# Temp_V_DC_Measurement.net
KiCad netlist of a schematic drawn in Altium Designer
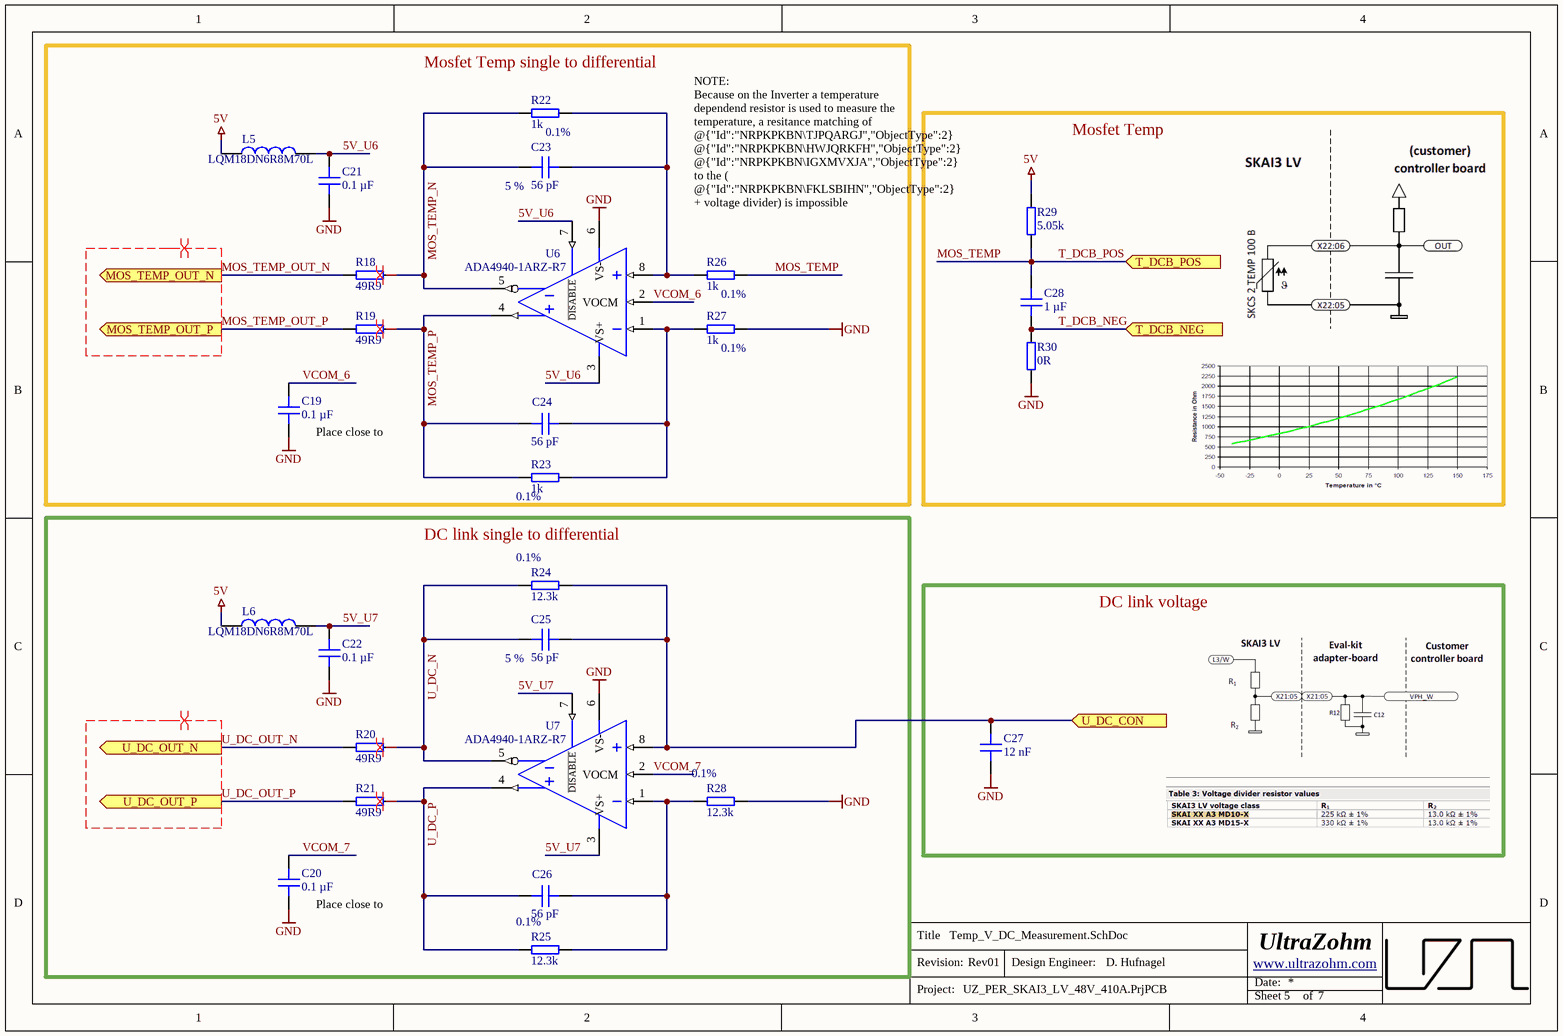
[diagram p0: Temp_V_DC_Measurement.SchDoc]

(export (version "E")
  (design (tool "Eeschema 10.0.6"))
  (components
    (comp (ref "C19")
      (value "0.1 µF")
      (footprint "C_0603")
      (description "Capacitor 0603, 50 VDC, 0.1 µF, X7R")
      (fields
        (field (name "MANUFACTURER PART NUMBER") "C0603X104K5RAC7411")
        (field (name "MANUFACTURER") "KEMET")
        (field (name "CREATED FROM") "MGremer")
      )
      (libsource (lib "user") (part "Capacitor"))
    )
    (comp (ref "C20")
      (value "0.1 µF")
      (footprint "C_0603")
      (description "Capacitor 0603, 50 VDC, 0.1 µF, X7R")
      (fields
        (field (name "MANUFACTURER PART NUMBER") "C0603X104K5RAC7411")
        (field (name "MANUFACTURER") "KEMET")
        (field (name "CREATED FROM") "MGremer")
      )
      (libsource (lib "user") (part "Capacitor"))
    )
    (comp (ref "C21")
      (value "0.1 µF")
      (footprint "C_0603")
      (description "Capacitor 0603, 50 VDC, 0.1 µF, X7R")
      (fields
        (field (name "MANUFACTURER PART NUMBER") "C0603X104K5RAC7411")
        (field (name "MANUFACTURER") "KEMET")
        (field (name "CREATED FROM") "MGremer")
      )
      (libsource (lib "user") (part "Capacitor"))
    )
    (comp (ref "C22")
      (value "0.1 µF")
      (footprint "C_0603")
      (description "Capacitor 0603, 50 VDC, 0.1 µF, X7R")
      (fields
        (field (name "MANUFACTURER PART NUMBER") "C0603X104K5RAC7411")
        (field (name "MANUFACTURER") "KEMET")
        (field (name "CREATED FROM") "MGremer")
      )
      (libsource (lib "user") (part "Capacitor"))
    )
    (comp (ref "C23")
      (value "56 pF")
      (footprint "C_0603")
      (description "Capacitor 0603, 50 VDC, 56 pF, C0G")
      (fields
        (field (name "MANUFACTURER PART NUMBER") "CL10C560JB8NNNC")
        (field (name "MANUFACTURER") "Samsung Electro-Mechanics")
        (field (name "TOLERANCE") "5 %")
        (field (name "CREATED FROM") "DHufnagel")
      )
      (libsource (lib "user") (part "Capacitor"))
    )
    (comp (ref "C24")
      (value "56 pF")
      (footprint "C_0603")
      (description "Capacitor 0603, 50 VDC, 56 pF, C0G")
      (fields
        (field (name "MANUFACTURER PART NUMBER") "CL10C560JB8NNNC")
        (field (name "MANUFACTURER") "Samsung Electro-Mechanics")
        (field (name "CREATED FROM") "DHufnagel")
      )
      (libsource (lib "user") (part "Capacitor"))
    )
    (comp (ref "C25")
      (value "56 pF")
      (footprint "C_0603")
      (description "Capacitor 0603, 50 VDC, 56 pF, C0G")
      (fields
        (field (name "MANUFACTURER PART NUMBER") "CL10C560JB8NNNC")
        (field (name "MANUFACTURER") "Samsung Electro-Mechanics")
        (field (name "TOLERANCE") "5 %")
        (field (name "CREATED FROM") "DHufnagel")
      )
      (libsource (lib "user") (part "Capacitor"))
    )
    (comp (ref "C26")
      (value "56 pF")
      (footprint "C_0603")
      (description "Capacitor 0603, 50 VDC, 56 pF, C0G")
      (fields
        (field (name "MANUFACTURER PART NUMBER") "CL10C560JB8NNNC")
        (field (name "MANUFACTURER") "Samsung Electro-Mechanics")
        (field (name "CREATED FROM") "DHufnagel")
      )
      (libsource (lib "user") (part "Capacitor"))
    )
    (comp (ref "C27")
      (value "12 nF")
      (footprint "C_0603")
      (description "Capacitor 0603, 16 VDC, 12 nF, X7R")
      (fields
        (field (name "MANUFACTURER PART NUMBER") "CC0603KRX7R7BB123")
        (field (name "MANUFACTURER") "Yageo")
        (field (name "CREATED FROM") "MGremer")
      )
      (libsource (lib "user") (part "Capacitor"))
    )
    (comp (ref "C28")
      (value "1 µF")
      (footprint "C_1206")
      (description "Capacitor 1206, 50 VDC, 1 µF, X7R")
      (fields
        (field (name "MANUFACTURER PART NUMBER") "C1206X105K5RECAUTO")
        (field (name "MANUFACTURER") "KEMET")
        (field (name "CREATED FROM") "MGremer")
      )
      (libsource (lib "user") (part "Capacitor"))
    )
    (comp (ref "L5")
      (value "LQM18DN6R8M70L")
      (footprint "INDC1608X95N")
      (description "6.8µH, 120mA, 0603, 740mOhm, 20%")
      (fields
        (field (name "MF") "EPCOS / TDK")
        (field (name "MPN") "B82464G4154M")
        (field (name "CREATED FROM") "DHufnagel")
      )
      (libsource (lib "user") (part "B82464G4154M"))
    )
    (comp (ref "L6")
      (value "LQM18DN6R8M70L")
      (footprint "INDC1608X95N")
      (description "6.8µH, 120mA, 0603, 740mOhm, 20%")
      (fields
        (field (name "MF") "EPCOS / TDK")
        (field (name "MPN") "B82464G4154M")
        (field (name "CREATED FROM") "DHufnagel")
      )
      (libsource (lib "user") (part "B82464G4154M"))
    )
    (comp (ref "R18")
      (value "49R9")
      (footprint "RES 0603_1608")
      (description "SMD resistor 1%")
      (fields
        (field (name "MANUFACTURER PART NUMBER") "RK73H1JTTD49R9F")
        (field (name "MANUFACTURER") "KOA Speer")
        (field (name "CREATED FROM") "DHufnagel")
      )
      (libsource (lib "user") (part "Resistor"))
    )
    (comp (ref "R19")
      (value "49R9")
      (footprint "RES 0603_1608")
      (description "SMD resistor 1%")
      (fields
        (field (name "MANUFACTURER PART NUMBER") "RK73H1JTTD49R9F")
        (field (name "MANUFACTURER") "KOA Speer")
        (field (name "CREATED FROM") "DHufnagel")
      )
      (libsource (lib "user") (part "Resistor"))
    )
    (comp (ref "R20")
      (value "49R9")
      (footprint "RES 0603_1608")
      (description "SMD resistor 1%")
      (fields
        (field (name "MANUFACTURER PART NUMBER") "RK73H1JTTD49R9F")
        (field (name "MANUFACTURER") "KOA Speer")
        (field (name "CREATED FROM") "DHufnagel")
      )
      (libsource (lib "user") (part "Resistor"))
    )
    (comp (ref "R21")
      (value "49R9")
      (footprint "RES 0603_1608")
      (description "SMD resistor 1%")
      (fields
        (field (name "MANUFACTURER PART NUMBER") "RK73H1JTTD49R9F")
        (field (name "MANUFACTURER") "KOA Speer")
        (field (name "CREATED FROM") "DHufnagel")
      )
      (libsource (lib "user") (part "Resistor"))
    )
    (comp (ref "R22")
      (value "1k")
      (footprint "RES 0603_1608")
      (description "SMD resistor 0.1%")
      (fields
        (field (name "MANUFACTURER PART NUMBER") "PCF-W0603LF-03-1001-B-P-LT")
        (field (name "MANUFACTURER") "IRC / TT Electronics")
        (field (name "TOLERANCE") "0.1%")
        (field (name "CREATED FROM") "MGremer")
      )
      (libsource (lib "user") (part "Resistor"))
    )
    (comp (ref "R23")
      (value "1k")
      (footprint "RES 0603_1608")
      (description "SMD resistor 0.1%")
      (fields
        (field (name "MANUFACTURER PART NUMBER") "PCF-W0603LF-03-1001-B-P-LT")
        (field (name "MANUFACTURER") "IRC / TT Electronics")
        (field (name "TOLERANCE") "0.1%")
        (field (name "CREATED FROM") "MGremer")
      )
      (libsource (lib "user") (part "Resistor"))
    )
    (comp (ref "R24")
      (value "12.3k")
      (footprint "RES 0603_1608")
      (description "SMD resistor E24 series 12 kOhms 100mW 0603 1%")
      (fields
        (field (name "MANUFACTURER PART NUMBER") "RT0603BRD0712K3L")
        (field (name "MANUFACTURER") "YAGEO")
        (field (name "TOLERANCE") "0.1%")
        (field (name "CREATED FROM") "DHufnagel")
      )
      (libsource (lib "user") (part "Resistor"))
    )
    (comp (ref "R25")
      (value "12.3k")
      (footprint "RES 0603_1608")
      (description "SMD resistor E24 series 12 kOhms 100mW 0603 1%")
      (fields
        (field (name "MANUFACTURER PART NUMBER") "RT0603BRD0712K3L")
        (field (name "MANUFACTURER") "YAGEO")
        (field (name "TOLERANCE") "0.1%")
        (field (name "CREATED FROM") "DHufnagel")
      )
      (libsource (lib "user") (part "Resistor"))
    )
    (comp (ref "R26")
      (value "1k")
      (footprint "RES 0603_1608")
      (description "SMD resistor 0.1%")
      (fields
        (field (name "MANUFACTURER PART NUMBER") "PCF-W0603LF-03-1001-B-P-LT")
        (field (name "MANUFACTURER") "IRC / TT Electronics")
        (field (name "TOLERANCE") "0.1%")
        (field (name "CREATED FROM") "MGremer")
      )
      (libsource (lib "user") (part "Resistor"))
    )
    (comp (ref "R27")
      (value "1k")
      (footprint "RES 0603_1608")
      (description "SMD resistor 0.1%")
      (fields
        (field (name "MANUFACTURER PART NUMBER") "PCF-W0603LF-03-1001-B-P-LT")
        (field (name "MANUFACTURER") "IRC / TT Electronics")
        (field (name "TOLERANCE") "0.1%")
        (field (name "CREATED FROM") "MGremer")
      )
      (libsource (lib "user") (part "Resistor"))
    )
    (comp (ref "R28")
      (value "12.3k")
      (footprint "RES 0603_1608")
      (description "SMD resistor E24 series 12 kOhms 100mW 0603 1%")
      (fields
        (field (name "MANUFACTURER PART NUMBER") "RT0603BRD0712K3L")
        (field (name "MANUFACTURER") "YAGEO")
        (field (name "TOLERANCE") "0.1%")
        (field (name "CREATED FROM") "DHufnagel")
      )
      (libsource (lib "user") (part "Resistor"))
    )
    (comp (ref "R29")
      (value "5.05k")
      (footprint "RES 0603_1608")
      (description "SMD resistor 0.1%")
      (fields
        (field (name "MANUFACTURER PART NUMBER") "TNPW06035K05BEEA")
        (field (name "MANUFACTURER") "Vishay")
        (field (name "CREATED FROM") "DHufnagel")
      )
      (libsource (lib "user") (part "Resistor"))
    )
    (comp (ref "R30")
      (value "0R")
      (footprint "RES 0603_1608")
      (description "SMD resistor E24 series")
      (fields
        (field (name "MANUFACTURER PART NUMBER") "RC0603JR-070RL")
        (field (name "MANUFACTURER") "YAGEO")
        (field (name "CREATED FROM") "MGremer")
      )
      (libsource (lib "user") (part "Resistor"))
    )
    (comp (ref "U6")
      (value "ADA4940-1ARZ-R7")
      (footprint "SOT127P600X175-8N")
      (description "Fully Differential Amplifier, Ultralow-Power,Low Distortion, 260-MHz")
      (fields
        (field (name "MANUFACTURER") "Analog Devices")
        (field (name "LCSC PART NUMBER") "C730049")
        (field (name "CREATED FROM") "DHufnagel")
      )
      (libsource (lib "user") (part "ADA4940-1ARZ"))
    )
    (comp (ref "U7")
      (value "ADA4940-1ARZ-R7")
      (footprint "SOT127P600X175-8N")
      (description "Fully Differential Amplifier, Ultralow-Power,Low Distortion, 260-MHz")
      (fields
        (field (name "MANUFACTURER") "Analog Devices")
        (field (name "LCSC PART NUMBER") "C730049")
        (field (name "CREATED FROM") "DHufnagel")
      )
      (libsource (lib "user") (part "ADA4940-1ARZ"))
    )
  )
  (nets
    (net (code "1") (name "/5V_U6") (class "Default")
      (node (ref "C21") (pin "2") (pinfunction "2_2") (pintype "passive"))
      (node (ref "L5") (pin "2") (pinfunction "2_2") (pintype "passive"))
      (node (ref "U6") (pin "3") (pinfunction "VS+_3") (pintype "power_in"))
      (node (ref "U6") (pin "7") (pinfunction "~{DISABLE}_7") (pintype "input"))
    )
    (net (code "2") (name "/5V_U7") (class "Default")
      (node (ref "C22") (pin "2") (pinfunction "2_2") (pintype "passive"))
      (node (ref "L6") (pin "2") (pinfunction "2_2") (pintype "passive"))
      (node (ref "U7") (pin "3") (pinfunction "VS+_3") (pintype "power_in"))
      (node (ref "U7") (pin "7") (pinfunction "~{DISABLE}_7") (pintype "input"))
    )
    (net (code "3") (name "/MOS_TEMP") (class "Default")
      (node (ref "C28") (pin "2") (pinfunction "2_2") (pintype "passive"))
      (node (ref "R26") (pin "1") (pinfunction "1_1") (pintype "passive"))
      (node (ref "R29") (pin "1") (pinfunction "1_1") (pintype "passive"))
    )
    (net (code "4") (name "/MOS_TEMP_N") (class "Default")
      (node (ref "C23") (pin "1") (pinfunction "1_1") (pintype "passive"))
      (node (ref "R18") (pin "2") (pinfunction "2_2") (pintype "passive"))
      (node (ref "R22") (pin "2") (pinfunction "2_2") (pintype "passive"))
      (node (ref "U6") (pin "5") (pinfunction "VOUT-_5") (pintype "output"))
    )
    (net (code "5") (name "/MOS_TEMP_OUT_N") (class "Default")
      (node (ref "R18") (pin "1") (pinfunction "1_1") (pintype "passive"))
    )
    (net (code "6") (name "/MOS_TEMP_OUT_P") (class "Default")
      (node (ref "R19") (pin "1") (pinfunction "1_1") (pintype "passive"))
    )
    (net (code "7") (name "/MOS_TEMP_P") (class "Default")
      (node (ref "C24") (pin "1") (pinfunction "1_1") (pintype "passive"))
      (node (ref "R19") (pin "2") (pinfunction "2_2") (pintype "passive"))
      (node (ref "R23") (pin "2") (pinfunction "2_2") (pintype "passive"))
      (node (ref "U6") (pin "4") (pinfunction "VOUT+_4") (pintype "output"))
    )
    (net (code "8") (name "/T_DCB_NEG") (class "Default")
      (node (ref "C28") (pin "1") (pinfunction "1_1") (pintype "passive"))
      (node (ref "R30") (pin "2") (pinfunction "2_2") (pintype "passive"))
    )
    (net (code "9") (name "/U_DC_CON") (class "Default")
      (node (ref "C25") (pin "2") (pinfunction "2_2") (pintype "passive"))
      (node (ref "C27") (pin "2") (pinfunction "2_2") (pintype "passive"))
      (node (ref "R24") (pin "2") (pinfunction "2_2") (pintype "passive"))
      (node (ref "U7") (pin "8") (pinfunction "VIN+_8") (pintype "input"))
    )
    (net (code "10") (name "/U_DC_N") (class "Default")
      (node (ref "C25") (pin "1") (pinfunction "1_1") (pintype "passive"))
      (node (ref "R20") (pin "2") (pinfunction "2_2") (pintype "passive"))
      (node (ref "R24") (pin "1") (pinfunction "1_1") (pintype "passive"))
      (node (ref "U7") (pin "5") (pinfunction "VOUT-_5") (pintype "output"))
    )
    (net (code "11") (name "/U_DC_OUT_N") (class "Default")
      (node (ref "R20") (pin "1") (pinfunction "1_1") (pintype "passive"))
    )
    (net (code "12") (name "/U_DC_OUT_P") (class "Default")
      (node (ref "R21") (pin "1") (pinfunction "1_1") (pintype "passive"))
    )
    (net (code "13") (name "/U_DC_P") (class "Default")
      (node (ref "C26") (pin "1") (pinfunction "1_1") (pintype "passive"))
      (node (ref "R21") (pin "2") (pinfunction "2_2") (pintype "passive"))
      (node (ref "R25") (pin "1") (pinfunction "1_1") (pintype "passive"))
      (node (ref "U7") (pin "4") (pinfunction "VOUT+_4") (pintype "output"))
    )
    (net (code "14") (name "/VCOM_6") (class "Default")
      (node (ref "C19") (pin "2") (pinfunction "2_2") (pintype "passive"))
      (node (ref "U6") (pin "2") (pinfunction "VOCM_2") (pintype "input"))
    )
    (net (code "15") (name "/VCOM_7") (class "Default")
      (node (ref "C20") (pin "2") (pinfunction "2_2") (pintype "passive"))
      (node (ref "U7") (pin "2") (pinfunction "VOCM_2") (pintype "input"))
    )
    (net (code "16") (name "5V") (class "Default")
      (node (ref "L5") (pin "1") (pinfunction "1_1") (pintype "passive"))
      (node (ref "L6") (pin "1") (pinfunction "1_1") (pintype "passive"))
      (node (ref "R29") (pin "2") (pinfunction "2_2") (pintype "passive"))
    )
    (net (code "17") (name "GND") (class "Default")
      (node (ref "C19") (pin "1") (pinfunction "1_1") (pintype "passive"))
      (node (ref "C20") (pin "1") (pinfunction "1_1") (pintype "passive"))
      (node (ref "C21") (pin "1") (pinfunction "1_1") (pintype "passive"))
      (node (ref "C22") (pin "1") (pinfunction "1_1") (pintype "passive"))
      (node (ref "C27") (pin "1") (pinfunction "1_1") (pintype "passive"))
      (node (ref "R27") (pin "1") (pinfunction "1_1") (pintype "passive"))
      (node (ref "R28") (pin "2") (pinfunction "2_2") (pintype "passive"))
      (node (ref "R30") (pin "1") (pinfunction "1_1") (pintype "passive"))
      (node (ref "U6") (pin "6") (pinfunction "VS-_6") (pintype "power_in"))
      (node (ref "U7") (pin "6") (pinfunction "VS-_6") (pintype "power_in"))
    )
    (net (code "18") (name "Net-(U6-VIN+)") (class "Default")
      (node (ref "C23") (pin "2") (pinfunction "2_2") (pintype "passive"))
      (node (ref "R22") (pin "1") (pinfunction "1_1") (pintype "passive"))
      (node (ref "R26") (pin "2") (pinfunction "2_2") (pintype "passive"))
      (node (ref "U6") (pin "8") (pinfunction "VIN+_8") (pintype "input"))
    )
    (net (code "19") (name "Net-(U6-VIN-)") (class "Default")
      (node (ref "C24") (pin "2") (pinfunction "2_2") (pintype "passive"))
      (node (ref "R23") (pin "1") (pinfunction "1_1") (pintype "passive"))
      (node (ref "R27") (pin "2") (pinfunction "2_2") (pintype "passive"))
      (node (ref "U6") (pin "1") (pinfunction "VIN-_1") (pintype "input"))
    )
    (net (code "20") (name "Net-(U7-VIN-)") (class "Default")
      (node (ref "C26") (pin "2") (pinfunction "2_2") (pintype "passive"))
      (node (ref "R25") (pin "2") (pinfunction "2_2") (pintype "passive"))
      (node (ref "R28") (pin "1") (pinfunction "1_1") (pintype "passive"))
      (node (ref "U7") (pin "1") (pinfunction "VIN-_1") (pintype "input"))
    )
  )
)
